# TGO.net
KiCad netlist of a schematic drawn in EAGLE
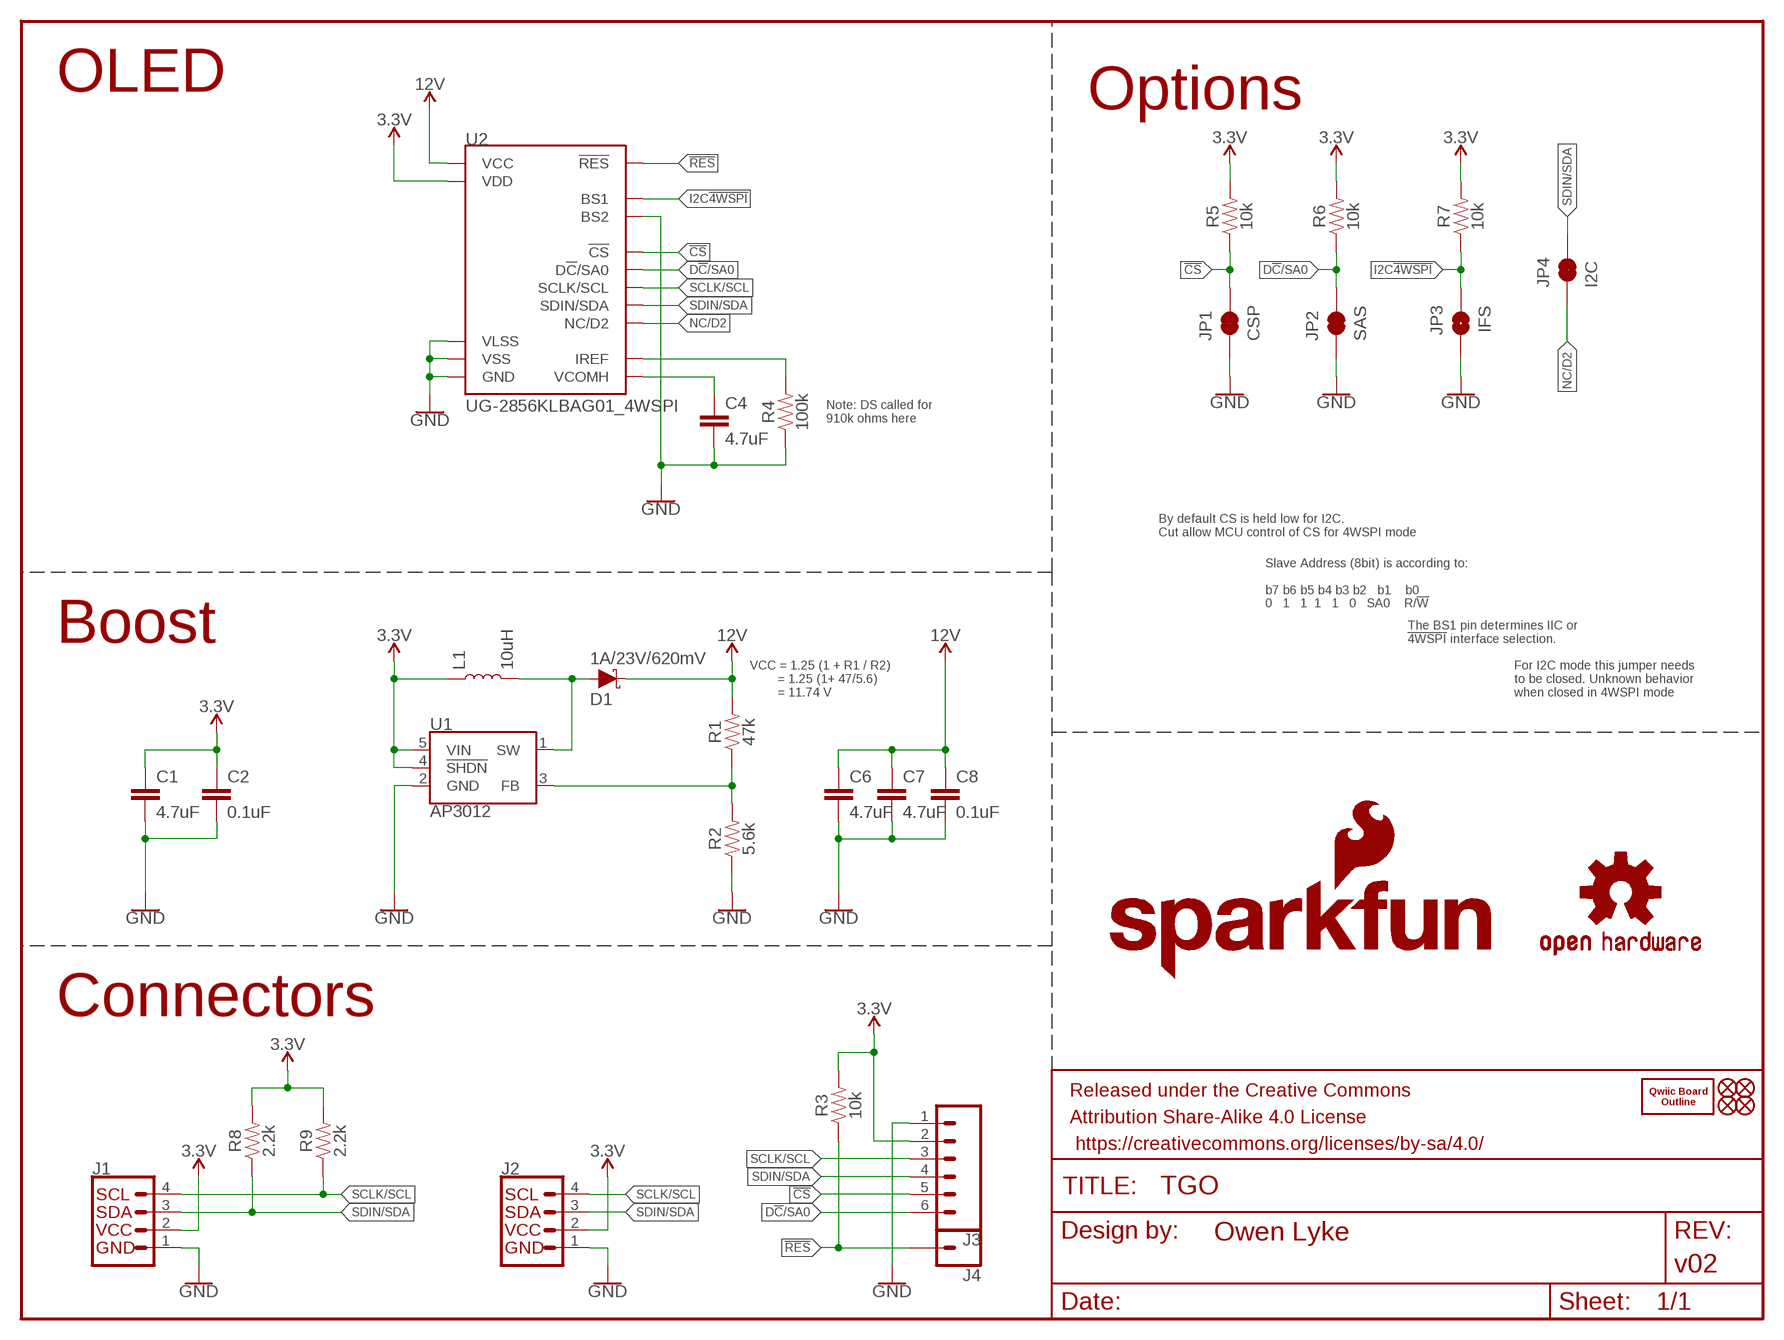
[diagram p0: schematic, sheet 1]

(export (version "E")
  (design (tool "Eeschema 10.0.6"))
  (components
    (comp (ref "C1")
      (value "4.7uF")
      (footprint "eagle-import:0603")
      (libsource (lib "eagle-import") (part "4.7UF-0603-35V-(20%)"))
    )
    (comp (ref "C2")
      (value "0.1uF")
      (footprint "eagle-import:0603")
      (libsource (lib "eagle-import") (part "0.1UF-0603-100V-10%"))
    )
    (comp (ref "C4")
      (value "4.7uF")
      (footprint "eagle-import:0603")
      (libsource (lib "eagle-import") (part "4.7UF-0603-35V-(20%)"))
    )
    (comp (ref "C6")
      (value "4.7uF")
      (footprint "eagle-import:0603")
      (libsource (lib "eagle-import") (part "4.7UF-0603-35V-(20%)"))
    )
    (comp (ref "C7")
      (value "4.7uF")
      (footprint "eagle-import:0603")
      (libsource (lib "eagle-import") (part "4.7UF-0603-35V-(20%)"))
    )
    (comp (ref "C8")
      (value "0.1uF")
      (footprint "eagle-import:0603")
      (libsource (lib "eagle-import") (part "0.1UF-0603-100V-10%"))
    )
    (comp (ref "D1")
      (value "1A/23V/620mV")
      (footprint "eagle-import:SOD-323")
      (libsource (lib "eagle-import") (part "DIODE-SCHOTTKY-BAT20J"))
    )
    (comp (ref "FD1")
      (value "FIDUCIAL1X2")
      (footprint "eagle-import:FIDUCIAL-1X2")
      (libsource (lib "eagle-import") (part "FIDUCIAL1X2"))
    )
    (comp (ref "FD2")
      (value "FIDUCIAL1X2")
      (footprint "eagle-import:FIDUCIAL-1X2")
      (libsource (lib "eagle-import") (part "FIDUCIAL1X2"))
    )
    (comp (ref "FD3")
      (value "FIDUCIAL1X2")
      (footprint "eagle-import:FIDUCIAL-1X2")
      (libsource (lib "eagle-import") (part "FIDUCIAL1X2"))
    )
    (comp (ref "FD4")
      (value "FIDUCIAL1X2")
      (footprint "eagle-import:FIDUCIAL-1X2")
      (libsource (lib "eagle-import") (part "FIDUCIAL1X2"))
    )
    (comp (ref "FRAME1")
      (value "FRAME-LETTER")
      (footprint "eagle-import:CREATIVE_COMMONS")
      (fields (field (name "DESIGNER") "Owen Lyke") (field (name "REV") "v02"))
      (libsource (lib "eagle-import") (part "FRAME-LETTER"))
    )
    (comp (ref "J1")
      (value "QWIIC_CONNECTORJS-1MM")
      (footprint "eagle-import:1X04_1MM_RA")
      (libsource (lib "eagle-import") (part "QWIIC_CONNECTORJS-1MM"))
    )
    (comp (ref "J2")
      (value "QWIIC_CONNECTORJS-1MM")
      (footprint "eagle-import:1X04_1MM_RA")
      (libsource (lib "eagle-import") (part "QWIIC_CONNECTORJS-1MM"))
    )
    (comp (ref "J3")
      (value "CONN_06NO_SILK_NO_POP")
      (footprint "eagle-import:1X06_NO_SILK")
      (libsource (lib "eagle-import") (part "CONN_06NO_SILK_NO_POP"))
    )
    (comp (ref "J4")
      (value "CONN_01PTH_NO_SILK_YES_STOP")
      (footprint "eagle-import:1X01_NO_SILK")
      (libsource (lib "eagle-import") (part "CONN_01PTH_NO_SILK_YES_STOP"))
    )
    (comp (ref "JP1")
      (value "CSP")
      (footprint "eagle-import:SMT-JUMPER_2_NC_TRACE_SILK")
      (libsource (lib "eagle-import") (part "JUMPER-SMT_2_NC_TRACE_SILK"))
    )
    (comp (ref "JP2")
      (value "SAS")
      (footprint "eagle-import:SMT-JUMPER_2_NC_TRACE_SILK")
      (libsource (lib "eagle-import") (part "JUMPER-SMT_2_NC_TRACE_SILK"))
    )
    (comp (ref "JP3")
      (value "IFS")
      (footprint "eagle-import:SMT-JUMPER_2_NO_SILK")
      (libsource (lib "eagle-import") (part "JUMPER-SMT_2_NO_SILK"))
    )
    (comp (ref "JP4")
      (value "I2C")
      (footprint "eagle-import:SMT-JUMPER_2_NC_TRACE_SILK")
      (libsource (lib "eagle-import") (part "JUMPER-SMT_2_NC_TRACE_SILK"))
    )
    (comp (ref "L1")
      (value "10uH")
      (footprint "eagle-import:INDUCTOR_4.7UH")
      (libsource (lib "eagle-import") (part "INDUCTOR-CDRH-10UH"))
    )
    (comp (ref "LOGO1")
      (value "SFE_LOGO_NAME_FLAME.1_INCH")
      (footprint "eagle-import:SFE_LOGO_NAME_FLAME_.1")
      (libsource (lib "eagle-import") (part "SFE_LOGO_NAME_FLAME.1_INCH"))
    )
    (comp (ref "LOGO2")
      (value "OSHW-LOGOS")
      (footprint "eagle-import:OSHW-LOGO-S")
      (libsource (lib "eagle-import") (part "OSHW-LOGOS"))
    )
    (comp (ref "R1")
      (value "47k")
      (footprint "eagle-import:0603")
      (libsource (lib "eagle-import") (part "47KOHM-0603-1/10W-1%"))
    )
    (comp (ref "R2")
      (value "5.6k")
      (footprint "eagle-import:0603")
      (libsource (lib "eagle-import") (part "5.6KOHM-0603-1/10W-1%"))
    )
    (comp (ref "R3")
      (value "10k")
      (footprint "eagle-import:0603")
      (libsource (lib "eagle-import") (part "10KOHM-0603-1/10W-1%"))
    )
    (comp (ref "R4")
      (value "100k")
      (footprint "eagle-import:0603")
      (libsource (lib "eagle-import") (part "100KOHM-0603-1/10W-1%"))
    )
    (comp (ref "R5")
      (value "10k")
      (footprint "eagle-import:0603")
      (libsource (lib "eagle-import") (part "10KOHM-0603-1/10W-1%"))
    )
    (comp (ref "R6")
      (value "10k")
      (footprint "eagle-import:0603")
      (libsource (lib "eagle-import") (part "10KOHM-0603-1/10W-1%"))
    )
    (comp (ref "R7")
      (value "10k")
      (footprint "eagle-import:0603")
      (libsource (lib "eagle-import") (part "10KOHM-0603-1/10W-1%"))
    )
    (comp (ref "R8")
      (value "2.2k")
      (footprint "eagle-import:0603")
      (libsource (lib "eagle-import") (part "2.2KOHM-0603-1/10W-1%"))
    )
    (comp (ref "R9")
      (value "2.2k")
      (footprint "eagle-import:0603")
      (libsource (lib "eagle-import") (part "2.2KOHM-0603-1/10W-1%"))
    )
    (comp (ref "U$1")
      (value "QWIIC_BOARD_OUTLINEH")
      (footprint "eagle-import:QWIIC_BOARD_MOUNT_HOLES")
      (libsource (lib "eagle-import") (part "QWIIC_BOARD_OUTLINEH"))
    )
    (comp (ref "U1")
      (value "AP3012")
      (footprint "eagle-import:SOT23-5")
      (libsource (lib "eagle-import") (part "AP3012"))
    )
    (comp (ref "U2")
      (value "UG-2856KLBAG01_4WSPI")
      (footprint "eagle-import:FPC05024-42201")
      (libsource (lib "eagle-import") (part "UG-2856KLBAG01_4WSPI"))
    )
  )
  (nets
    (net (code "1") (name "/D~{C}{slash}SA0") (class "Default")
      (node (ref "J3") (pin "6") (pinfunction "6_6") (pintype "passive"))
      (node (ref "JP2") (pin "2") (pinfunction "2_2") (pintype "passive"))
      (node (ref "R6") (pin "1") (pinfunction "1_1") (pintype "passive"))
      (node (ref "U2") (pin "P$10") (pinfunction "D~{C}/SA0_P$10") (pintype "bidirectional"))
    )
    (net (code "2") (name "/I2C~{4WSPI}") (class "Default")
      (node (ref "JP3") (pin "1") (pinfunction "1_1") (pintype "passive"))
      (node (ref "R7") (pin "1") (pinfunction "1_1") (pintype "passive"))
      (node (ref "U2") (pin "P$6") (pinfunction "BS1_P$6") (pintype "bidirectional"))
    )
    (net (code "3") (name "/~{CS}") (class "Default")
      (node (ref "J3") (pin "5") (pinfunction "5_5") (pintype "passive"))
      (node (ref "JP1") (pin "2") (pinfunction "2_2") (pintype "passive"))
      (node (ref "R5") (pin "1") (pinfunction "1_1") (pintype "passive"))
      (node (ref "U2") (pin "P$8") (pinfunction "~{CS}_P$8") (pintype "bidirectional"))
    )
    (net (code "4") (name "/~{RES}") (class "Default")
      (node (ref "J4") (pin "1") (pinfunction "1_1") (pintype "passive"))
      (node (ref "R3") (pin "1") (pinfunction "1_1") (pintype "passive"))
      (node (ref "U2") (pin "P$9") (pinfunction "~{RES}_P$9") (pintype "bidirectional"))
    )
    (net (code "5") (name "3.3V") (class "Default")
      (node (ref "C1") (pin "1") (pinfunction "1_1") (pintype "passive"))
      (node (ref "C2") (pin "1") (pinfunction "1_1") (pintype "passive"))
      (node (ref "J1") (pin "2") (pinfunction "2_2") (pintype "power_in"))
      (node (ref "J2") (pin "2") (pinfunction "2_2") (pintype "power_in"))
      (node (ref "J3") (pin "2") (pinfunction "2_2") (pintype "passive"))
      (node (ref "L1") (pin "P$1") (pinfunction "1_P$1") (pintype "passive"))
      (node (ref "R3") (pin "2") (pinfunction "2_2") (pintype "passive"))
      (node (ref "R5") (pin "2") (pinfunction "2_2") (pintype "passive"))
      (node (ref "R6") (pin "2") (pinfunction "2_2") (pintype "passive"))
      (node (ref "R7") (pin "2") (pinfunction "2_2") (pintype "passive"))
      (node (ref "R8") (pin "2") (pinfunction "2_2") (pintype "passive"))
      (node (ref "R9") (pin "2") (pinfunction "2_2") (pintype "passive"))
      (node (ref "U1") (pin "4") (pinfunction "~{SHDN}_4") (pintype "bidirectional"))
      (node (ref "U1") (pin "5") (pinfunction "VIN_5") (pintype "bidirectional"))
      (node (ref "U2") (pin "P$5") (pinfunction "VDD_P$5") (pintype "bidirectional"))
    )
    (net (code "6") (name "12V") (class "Default")
      (node (ref "C6") (pin "1") (pinfunction "1_1") (pintype "passive"))
      (node (ref "C7") (pin "1") (pinfunction "1_1") (pintype "passive"))
      (node (ref "C8") (pin "1") (pinfunction "1_1") (pintype "passive"))
      (node (ref "D1") (pin "C") (pinfunction "C_C") (pintype "passive"))
      (node (ref "R1") (pin "2") (pinfunction "2_2") (pintype "passive"))
      (node (ref "U2") (pin "P$23") (pinfunction "VCC_P$23") (pintype "bidirectional"))
    )
    (net (code "7") (name "GND") (class "Default")
      (node (ref "C1") (pin "2") (pinfunction "2_2") (pintype "passive"))
      (node (ref "C2") (pin "2") (pinfunction "2_2") (pintype "passive"))
      (node (ref "C4") (pin "2") (pinfunction "2_2") (pintype "passive"))
      (node (ref "C6") (pin "2") (pinfunction "2_2") (pintype "passive"))
      (node (ref "C7") (pin "2") (pinfunction "2_2") (pintype "passive"))
      (node (ref "C8") (pin "2") (pinfunction "2_2") (pintype "passive"))
      (node (ref "J1") (pin "1") (pinfunction "1_1") (pintype "power_in"))
      (node (ref "J2") (pin "1") (pinfunction "1_1") (pintype "power_in"))
      (node (ref "J3") (pin "1") (pinfunction "1_1") (pintype "passive"))
      (node (ref "JP1") (pin "1") (pinfunction "1_1") (pintype "passive"))
      (node (ref "JP2") (pin "1") (pinfunction "1_1") (pintype "passive"))
      (node (ref "JP3") (pin "2") (pinfunction "2_2") (pintype "passive"))
      (node (ref "R2") (pin "1") (pinfunction "1_1") (pintype "passive"))
      (node (ref "R4") (pin "1") (pinfunction "1_1") (pintype "passive"))
      (node (ref "U1") (pin "2") (pinfunction "GND_2") (pintype "bidirectional"))
      (node (ref "U2") (pin "P$1") (pinfunction "GND_P$1") (pintype "bidirectional"))
      (node (ref "U2") (pin "P$11") (pinfunction "GND_P$11") (pintype "bidirectional"))
      (node (ref "U2") (pin "P$12") (pinfunction "GND_P$12") (pintype "bidirectional"))
      (node (ref "U2") (pin "P$16") (pinfunction "GND_P$16") (pintype "bidirectional"))
      (node (ref "U2") (pin "P$17") (pinfunction "GND_P$17") (pintype "bidirectional"))
      (node (ref "U2") (pin "P$18") (pinfunction "GND_P$18") (pintype "bidirectional"))
      (node (ref "U2") (pin "P$19") (pinfunction "GND_P$19") (pintype "bidirectional"))
      (node (ref "U2") (pin "P$2") (pinfunction "VLSS_P$2") (pintype "bidirectional"))
      (node (ref "U2") (pin "P$20") (pinfunction "GND_P$20") (pintype "bidirectional"))
      (node (ref "U2") (pin "P$24") (pinfunction "GND_P$24") (pintype "bidirectional"))
      (node (ref "U2") (pin "P$3") (pinfunction "VSS_P$3") (pintype "bidirectional"))
      (node (ref "U2") (pin "P$7") (pinfunction "BS2_P$7") (pintype "bidirectional"))
    )
    (net (code "8") (name "NC{slash}D2") (class "Default")
      (node (ref "JP4") (pin "1") (pinfunction "1_1") (pintype "passive"))
      (node (ref "U2") (pin "P$15") (pinfunction "NC/D2_P$15") (pintype "bidirectional"))
    )
    (net (code "9") (name "Net-(L1-2)") (class "Default")
      (node (ref "D1") (pin "A") (pinfunction "A_A") (pintype "passive"))
      (node (ref "L1") (pin "P$2") (pinfunction "2_P$2") (pintype "passive"))
      (node (ref "U1") (pin "1") (pinfunction "SW_1") (pintype "bidirectional"))
    )
    (net (code "10") (name "Net-(U1-FB)") (class "Default")
      (node (ref "R1") (pin "1") (pinfunction "1_1") (pintype "passive"))
      (node (ref "R2") (pin "2") (pinfunction "2_2") (pintype "passive"))
      (node (ref "U1") (pin "3") (pinfunction "FB_3") (pintype "bidirectional"))
    )
    (net (code "11") (name "Net-(U2-IREF)") (class "Default")
      (node (ref "R4") (pin "2") (pinfunction "2_2") (pintype "passive"))
      (node (ref "U2") (pin "P$21") (pinfunction "IREF_P$21") (pintype "bidirectional"))
    )
    (net (code "12") (name "Net-(U2-VCOMH)") (class "Default")
      (node (ref "C4") (pin "1") (pinfunction "1_1") (pintype "passive"))
      (node (ref "U2") (pin "P$22") (pinfunction "VCOMH_P$22") (pintype "bidirectional"))
    )
    (net (code "13") (name "SCLK{slash}SCL") (class "Default")
      (node (ref "J1") (pin "4") (pinfunction "4_4") (pintype "passive"))
      (node (ref "J2") (pin "4") (pinfunction "4_4") (pintype "passive"))
      (node (ref "J3") (pin "3") (pinfunction "3_3") (pintype "passive"))
      (node (ref "R9") (pin "1") (pinfunction "1_1") (pintype "passive"))
      (node (ref "U2") (pin "P$13") (pinfunction "SCLK/SCL_P$13") (pintype "bidirectional"))
    )
    (net (code "14") (name "SDIN{slash}SDA") (class "Default")
      (node (ref "J1") (pin "3") (pinfunction "3_3") (pintype "passive"))
      (node (ref "J2") (pin "3") (pinfunction "3_3") (pintype "passive"))
      (node (ref "J3") (pin "4") (pinfunction "4_4") (pintype "passive"))
      (node (ref "JP4") (pin "2") (pinfunction "2_2") (pintype "passive"))
      (node (ref "R8") (pin "1") (pinfunction "1_1") (pintype "passive"))
      (node (ref "U2") (pin "P$14") (pinfunction "SDIN/SDA_P$14") (pintype "bidirectional"))
    )
  )
)
